# fd_principal.net
KiCad netlist of a schematic drawn in EAGLE
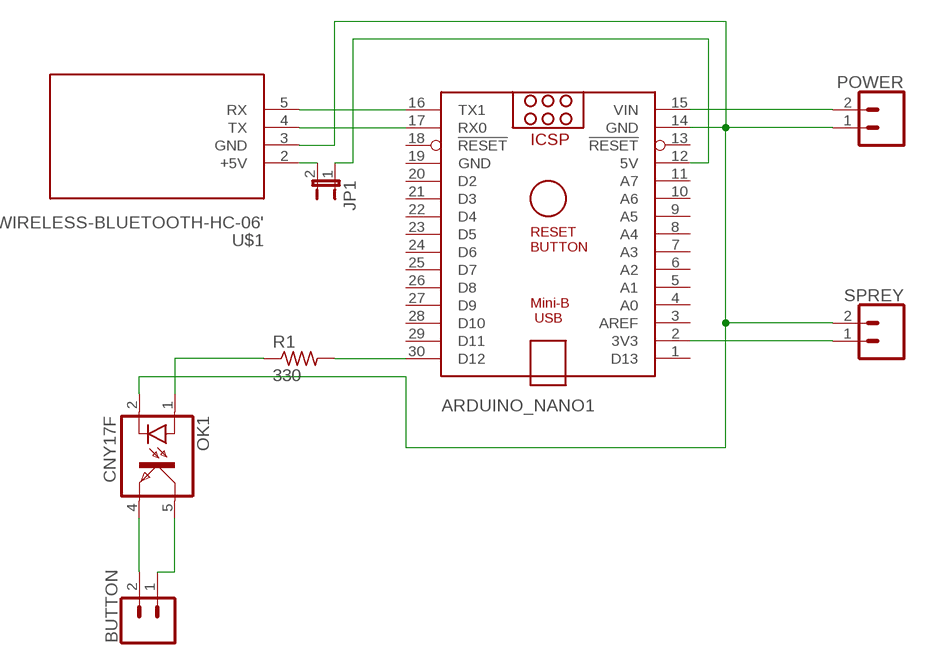
[diagram p0: schematic, sheet 1]

(export (version "E")
  (design (tool "Eeschema 10.0.6"))
  (components
    (comp (ref "ARDUINO_NANO1")
      (value "ARDUINO_NANO")
      (footprint "eagle-import:ARDUINO_NANO")
      (libsource (lib "eagle-import") (part "ARDUINO_NANO"))
    )
    (comp (ref "BUTTON")
      (value "CONN_025MM")
      (footprint "eagle-import:SCREWTERMINAL-5MM-2")
      (libsource (lib "eagle-import") (part "CONN_025MM"))
    )
    (comp (ref "JP1")
      (value "JP1E")
      (footprint "eagle-import:JP1")
      (libsource (lib "eagle-import") (part "JP1E"))
    )
    (comp (ref "OK1")
      (value "CNY17F")
      (footprint "eagle-import:DIL06")
      (fields (field (name "MF") "VISHAY/TELEFUNKEN") (field (name "MPN") "CNY17F-3"))
      (libsource (lib "eagle-import") (part "CNY17F"))
    )
    (comp (ref "POWER")
      (value "CONN_025MM")
      (footprint "eagle-import:SCREWTERMINAL-5MM-2")
      (libsource (lib "eagle-import") (part "CONN_025MM"))
    )
    (comp (ref "R1")
      (value "330")
      (footprint "eagle-import:0207_10")
      (libsource (lib "eagle-import") (part "R-US_0207/10"))
    )
    (comp (ref "SPREY")
      (value "CONN_025MM")
      (footprint "eagle-import:SCREWTERMINAL-5MM-2")
      (libsource (lib "eagle-import") (part "CONN_025MM"))
    )
    (comp (ref "U$1")
      (value "WIRELESS-BLUETOOTH-HC-06'")
      (footprint "eagle-import:WIRELESS-BLUETOOTH-HC-06")
      (libsource (lib "eagle-import") (part "WIRELESS-BLUETOOTH-HC-06'"))
    )
  )
  (nets
    (net (code "1") (name "/GND") (class "Default")
      (node (ref "ARDUINO_NANO1") (pin "19") (pinfunction "GND_19") (pintype "power_in"))
    )
    (net (code "2") (name "Net-(ARDUINO_NANO1-3V3)") (class "Default")
      (node (ref "ARDUINO_NANO1") (pin "2") (pinfunction "3V3_2") (pintype "output"))
      (node (ref "SPREY") (pin "1") (pinfunction "1_1") (pintype "passive"))
    )
    (net (code "3") (name "Net-(ARDUINO_NANO1-5V)") (class "Default")
      (node (ref "ARDUINO_NANO1") (pin "12") (pinfunction "5V_12") (pintype "power_in"))
      (node (ref "JP1") (pin "1") (pinfunction "1_1") (pintype "passive"))
    )
    (net (code "4") (name "Net-(ARDUINO_NANO1-D12)") (class "Default")
      (node (ref "ARDUINO_NANO1") (pin "30") (pinfunction "D12_30") (pintype "bidirectional"))
      (node (ref "R1") (pin "2") (pinfunction "2_2") (pintype "passive"))
    )
    (net (code "5") (name "Net-(ARDUINO_NANO1-RX0)") (class "Default")
      (node (ref "ARDUINO_NANO1") (pin "17") (pinfunction "RX0_17") (pintype "bidirectional"))
      (node (ref "U$1") (pin "4") (pinfunction "TX_4") (pintype "bidirectional"))
    )
    (net (code "6") (name "Net-(ARDUINO_NANO1-TX1)") (class "Default")
      (node (ref "ARDUINO_NANO1") (pin "16") (pinfunction "TX1_16") (pintype "bidirectional"))
      (node (ref "U$1") (pin "5") (pinfunction "RX_5") (pintype "bidirectional"))
    )
    (net (code "7") (name "Net-(ARDUINO_NANO1-VIN)") (class "Default")
      (node (ref "ARDUINO_NANO1") (pin "15") (pinfunction "VIN_15") (pintype "power_in"))
      (node (ref "POWER") (pin "2") (pinfunction "2_2") (pintype "passive"))
    )
    (net (code "8") (name "Net-(OK1-A)") (class "Default")
      (node (ref "OK1") (pin "1") (pinfunction "A_1") (pintype "passive"))
      (node (ref "R1") (pin "1") (pinfunction "1_1") (pintype "passive"))
    )
    (net (code "9") (name "Net-(OK1-C)") (class "Default")
      (node (ref "ARDUINO_NANO1") (pin "14") (pinfunction "GND_14") (pintype "power_in"))
      (node (ref "OK1") (pin "2") (pinfunction "C_2") (pintype "passive"))
      (node (ref "POWER") (pin "1") (pinfunction "1_1") (pintype "passive"))
      (node (ref "SPREY") (pin "2") (pinfunction "2_2") (pintype "passive"))
      (node (ref "U$1") (pin "3") (pinfunction "GND_3") (pintype "power_in"))
    )
    (net (code "10") (name "Net-(OK1-COL)") (class "Default")
      (node (ref "BUTTON") (pin "1") (pinfunction "1_1") (pintype "passive"))
      (node (ref "OK1") (pin "5") (pinfunction "COL_5") (pintype "passive"))
    )
    (net (code "11") (name "Net-(OK1-EMIT)") (class "Default")
      (node (ref "BUTTON") (pin "2") (pinfunction "2_2") (pintype "passive"))
      (node (ref "OK1") (pin "4") (pinfunction "EMIT_4") (pintype "passive"))
    )
    (net (code "12") (name "Net-(U$1-+5V)") (class "Default")
      (node (ref "JP1") (pin "2") (pinfunction "2_2") (pintype "passive"))
      (node (ref "U$1") (pin "2") (pinfunction "+5V_2") (pintype "power_in"))
    )
    (net (code "13") (name "unconnected-(ARDUINO_NANO1-A0-Pad4)") (class "Default")
      (node (ref "ARDUINO_NANO1") (pin "4") (pinfunction "A0_4") (pintype "bidirectional"))
    )
    (net (code "14") (name "unconnected-(ARDUINO_NANO1-A1-Pad5)") (class "Default")
      (node (ref "ARDUINO_NANO1") (pin "5") (pinfunction "A1_5") (pintype "bidirectional"))
    )
    (net (code "15") (name "unconnected-(ARDUINO_NANO1-A2-Pad6)") (class "Default")
      (node (ref "ARDUINO_NANO1") (pin "6") (pinfunction "A2_6") (pintype "bidirectional"))
    )
    (net (code "16") (name "unconnected-(ARDUINO_NANO1-A3-Pad7)") (class "Default")
      (node (ref "ARDUINO_NANO1") (pin "7") (pinfunction "A3_7") (pintype "bidirectional"))
    )
    (net (code "17") (name "unconnected-(ARDUINO_NANO1-A4-Pad8)") (class "Default")
      (node (ref "ARDUINO_NANO1") (pin "8") (pinfunction "A4_8") (pintype "bidirectional"))
    )
    (net (code "18") (name "unconnected-(ARDUINO_NANO1-A5-Pad9)") (class "Default")
      (node (ref "ARDUINO_NANO1") (pin "9") (pinfunction "A5_9") (pintype "bidirectional"))
    )
    (net (code "19") (name "unconnected-(ARDUINO_NANO1-A6-Pad10)") (class "Default")
      (node (ref "ARDUINO_NANO1") (pin "10") (pinfunction "A6_10") (pintype "bidirectional"))
    )
    (net (code "20") (name "unconnected-(ARDUINO_NANO1-A7-Pad11)") (class "Default")
      (node (ref "ARDUINO_NANO1") (pin "11") (pinfunction "A7_11") (pintype "bidirectional"))
    )
    (net (code "21") (name "unconnected-(ARDUINO_NANO1-AREF-Pad3)") (class "Default")
      (node (ref "ARDUINO_NANO1") (pin "3") (pinfunction "AREF_3") (pintype "input"))
    )
    (net (code "22") (name "unconnected-(ARDUINO_NANO1-D2-Pad20)") (class "Default")
      (node (ref "ARDUINO_NANO1") (pin "20") (pinfunction "D2_20") (pintype "bidirectional"))
    )
    (net (code "23") (name "unconnected-(ARDUINO_NANO1-D3-Pad21)") (class "Default")
      (node (ref "ARDUINO_NANO1") (pin "21") (pinfunction "D3_21") (pintype "bidirectional"))
    )
    (net (code "24") (name "unconnected-(ARDUINO_NANO1-D4-Pad22)") (class "Default")
      (node (ref "ARDUINO_NANO1") (pin "22") (pinfunction "D4_22") (pintype "bidirectional"))
    )
    (net (code "25") (name "unconnected-(ARDUINO_NANO1-D5-Pad23)") (class "Default")
      (node (ref "ARDUINO_NANO1") (pin "23") (pinfunction "D5_23") (pintype "bidirectional"))
    )
    (net (code "26") (name "unconnected-(ARDUINO_NANO1-D6-Pad24)") (class "Default")
      (node (ref "ARDUINO_NANO1") (pin "24") (pinfunction "D6_24") (pintype "bidirectional"))
    )
    (net (code "27") (name "unconnected-(ARDUINO_NANO1-D7-Pad25)") (class "Default")
      (node (ref "ARDUINO_NANO1") (pin "25") (pinfunction "D7_25") (pintype "bidirectional"))
    )
    (net (code "28") (name "unconnected-(ARDUINO_NANO1-D8-Pad26)") (class "Default")
      (node (ref "ARDUINO_NANO1") (pin "26") (pinfunction "D8_26") (pintype "bidirectional"))
    )
    (net (code "29") (name "unconnected-(ARDUINO_NANO1-D9-Pad27)") (class "Default")
      (node (ref "ARDUINO_NANO1") (pin "27") (pinfunction "D9_27") (pintype "bidirectional"))
    )
    (net (code "30") (name "unconnected-(ARDUINO_NANO1-D10-Pad28)") (class "Default")
      (node (ref "ARDUINO_NANO1") (pin "28") (pinfunction "D10_28") (pintype "bidirectional"))
    )
    (net (code "31") (name "unconnected-(ARDUINO_NANO1-D11-Pad29)") (class "Default")
      (node (ref "ARDUINO_NANO1") (pin "29") (pinfunction "D11_29") (pintype "bidirectional"))
    )
    (net (code "32") (name "unconnected-(ARDUINO_NANO1-D13-Pad1)") (class "Default")
      (node (ref "ARDUINO_NANO1") (pin "1") (pinfunction "D13_1") (pintype "bidirectional"))
    )
    (net (code "33") (name "unconnected-(ARDUINO_NANO1-~{RESET}-Pad13)") (class "Default")
      (node (ref "ARDUINO_NANO1") (pin "13") (pinfunction "~{RESET}_13") (pintype "input"))
    )
    (net (code "34") (name "unconnected-(ARDUINO_NANO1-~{RESET}-Pad18)") (class "Default")
      (node (ref "ARDUINO_NANO1") (pin "18") (pinfunction "~{RESET}_18") (pintype "input"))
    )
  )
)
